# ptn78000w.net
KiCad netlist of a schematic drawn in EAGLE
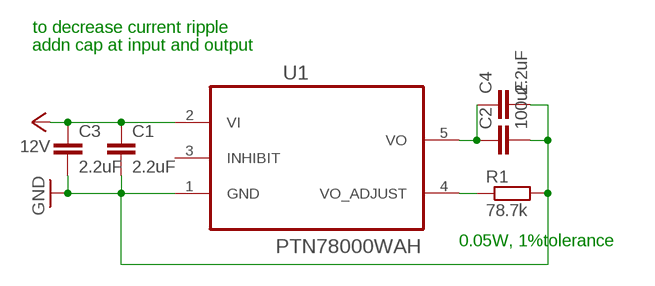
[diagram p0: schematic, sheet 1]

(export (version "E")
  (design (tool "Eeschema 10.0.6"))
  (components
    (comp (ref "C1")
      (value "2.2uF")
      (footprint "eagle-import:C0805")
      (libsource (lib "eagle-import") (part "C-EUC0805"))
    )
    (comp (ref "C2")
      (value "100uF")
      (footprint "eagle-import:C0805")
      (libsource (lib "eagle-import") (part "C-EUC0805"))
    )
    (comp (ref "C3")
      (value "2.2uF")
      (footprint "eagle-import:C0805")
      (libsource (lib "eagle-import") (part "C-EUC0805"))
    )
    (comp (ref "C4")
      (value "2.2uF")
      (footprint "eagle-import:C0805")
      (libsource (lib "eagle-import") (part "C-EUC0805"))
    )
    (comp (ref "R1")
      (value "78.7k")
      (footprint "eagle-import:R0805")
      (libsource (lib "eagle-import") (part "R-EU_R0805"))
    )
    (comp (ref "U1")
      (value "PTN78000WAH")
      (footprint "eagle-import:TI_PTN78000WAH")
      (libsource (lib "eagle-import") (part "PTN78000WAH"))
    )
  )
  (nets
    (net (code "1") (name "12V") (class "Default")
      (node (ref "C1") (pin "1") (pinfunction "1_1") (pintype "passive"))
      (node (ref "C3") (pin "1") (pinfunction "1_1") (pintype "passive"))
      (node (ref "U1") (pin "2") (pinfunction "VI_2") (pintype "input"))
    )
    (net (code "2") (name "GND") (class "Default")
      (node (ref "C1") (pin "2") (pinfunction "2_2") (pintype "passive"))
      (node (ref "C2") (pin "2") (pinfunction "2_2") (pintype "passive"))
      (node (ref "C3") (pin "2") (pinfunction "2_2") (pintype "passive"))
      (node (ref "C4") (pin "2") (pinfunction "2_2") (pintype "passive"))
      (node (ref "R1") (pin "2") (pinfunction "2_2") (pintype "passive"))
      (node (ref "U1") (pin "1") (pinfunction "GND_1") (pintype "bidirectional"))
    )
    (net (code "3") (name "Net-(U1-VO)") (class "Default")
      (node (ref "C2") (pin "1") (pinfunction "1_1") (pintype "passive"))
      (node (ref "C4") (pin "1") (pinfunction "1_1") (pintype "passive"))
      (node (ref "U1") (pin "5") (pinfunction "VO_5") (pintype "output"))
    )
    (net (code "4") (name "Net-(U1-VO_ADJUST)") (class "Default")
      (node (ref "R1") (pin "1") (pinfunction "1_1") (pintype "passive"))
      (node (ref "U1") (pin "4") (pinfunction "VO_ADJUST_4") (pintype "output"))
    )
    (net (code "5") (name "unconnected-(U1-INHIBIT-Pad3)") (class "Default")
      (node (ref "U1") (pin "3") (pinfunction "INHIBIT_3") (pintype "input"))
    )
  )
)
